# SCH_updated.net
KiCad netlist of a schematic drawn in EasyEDA
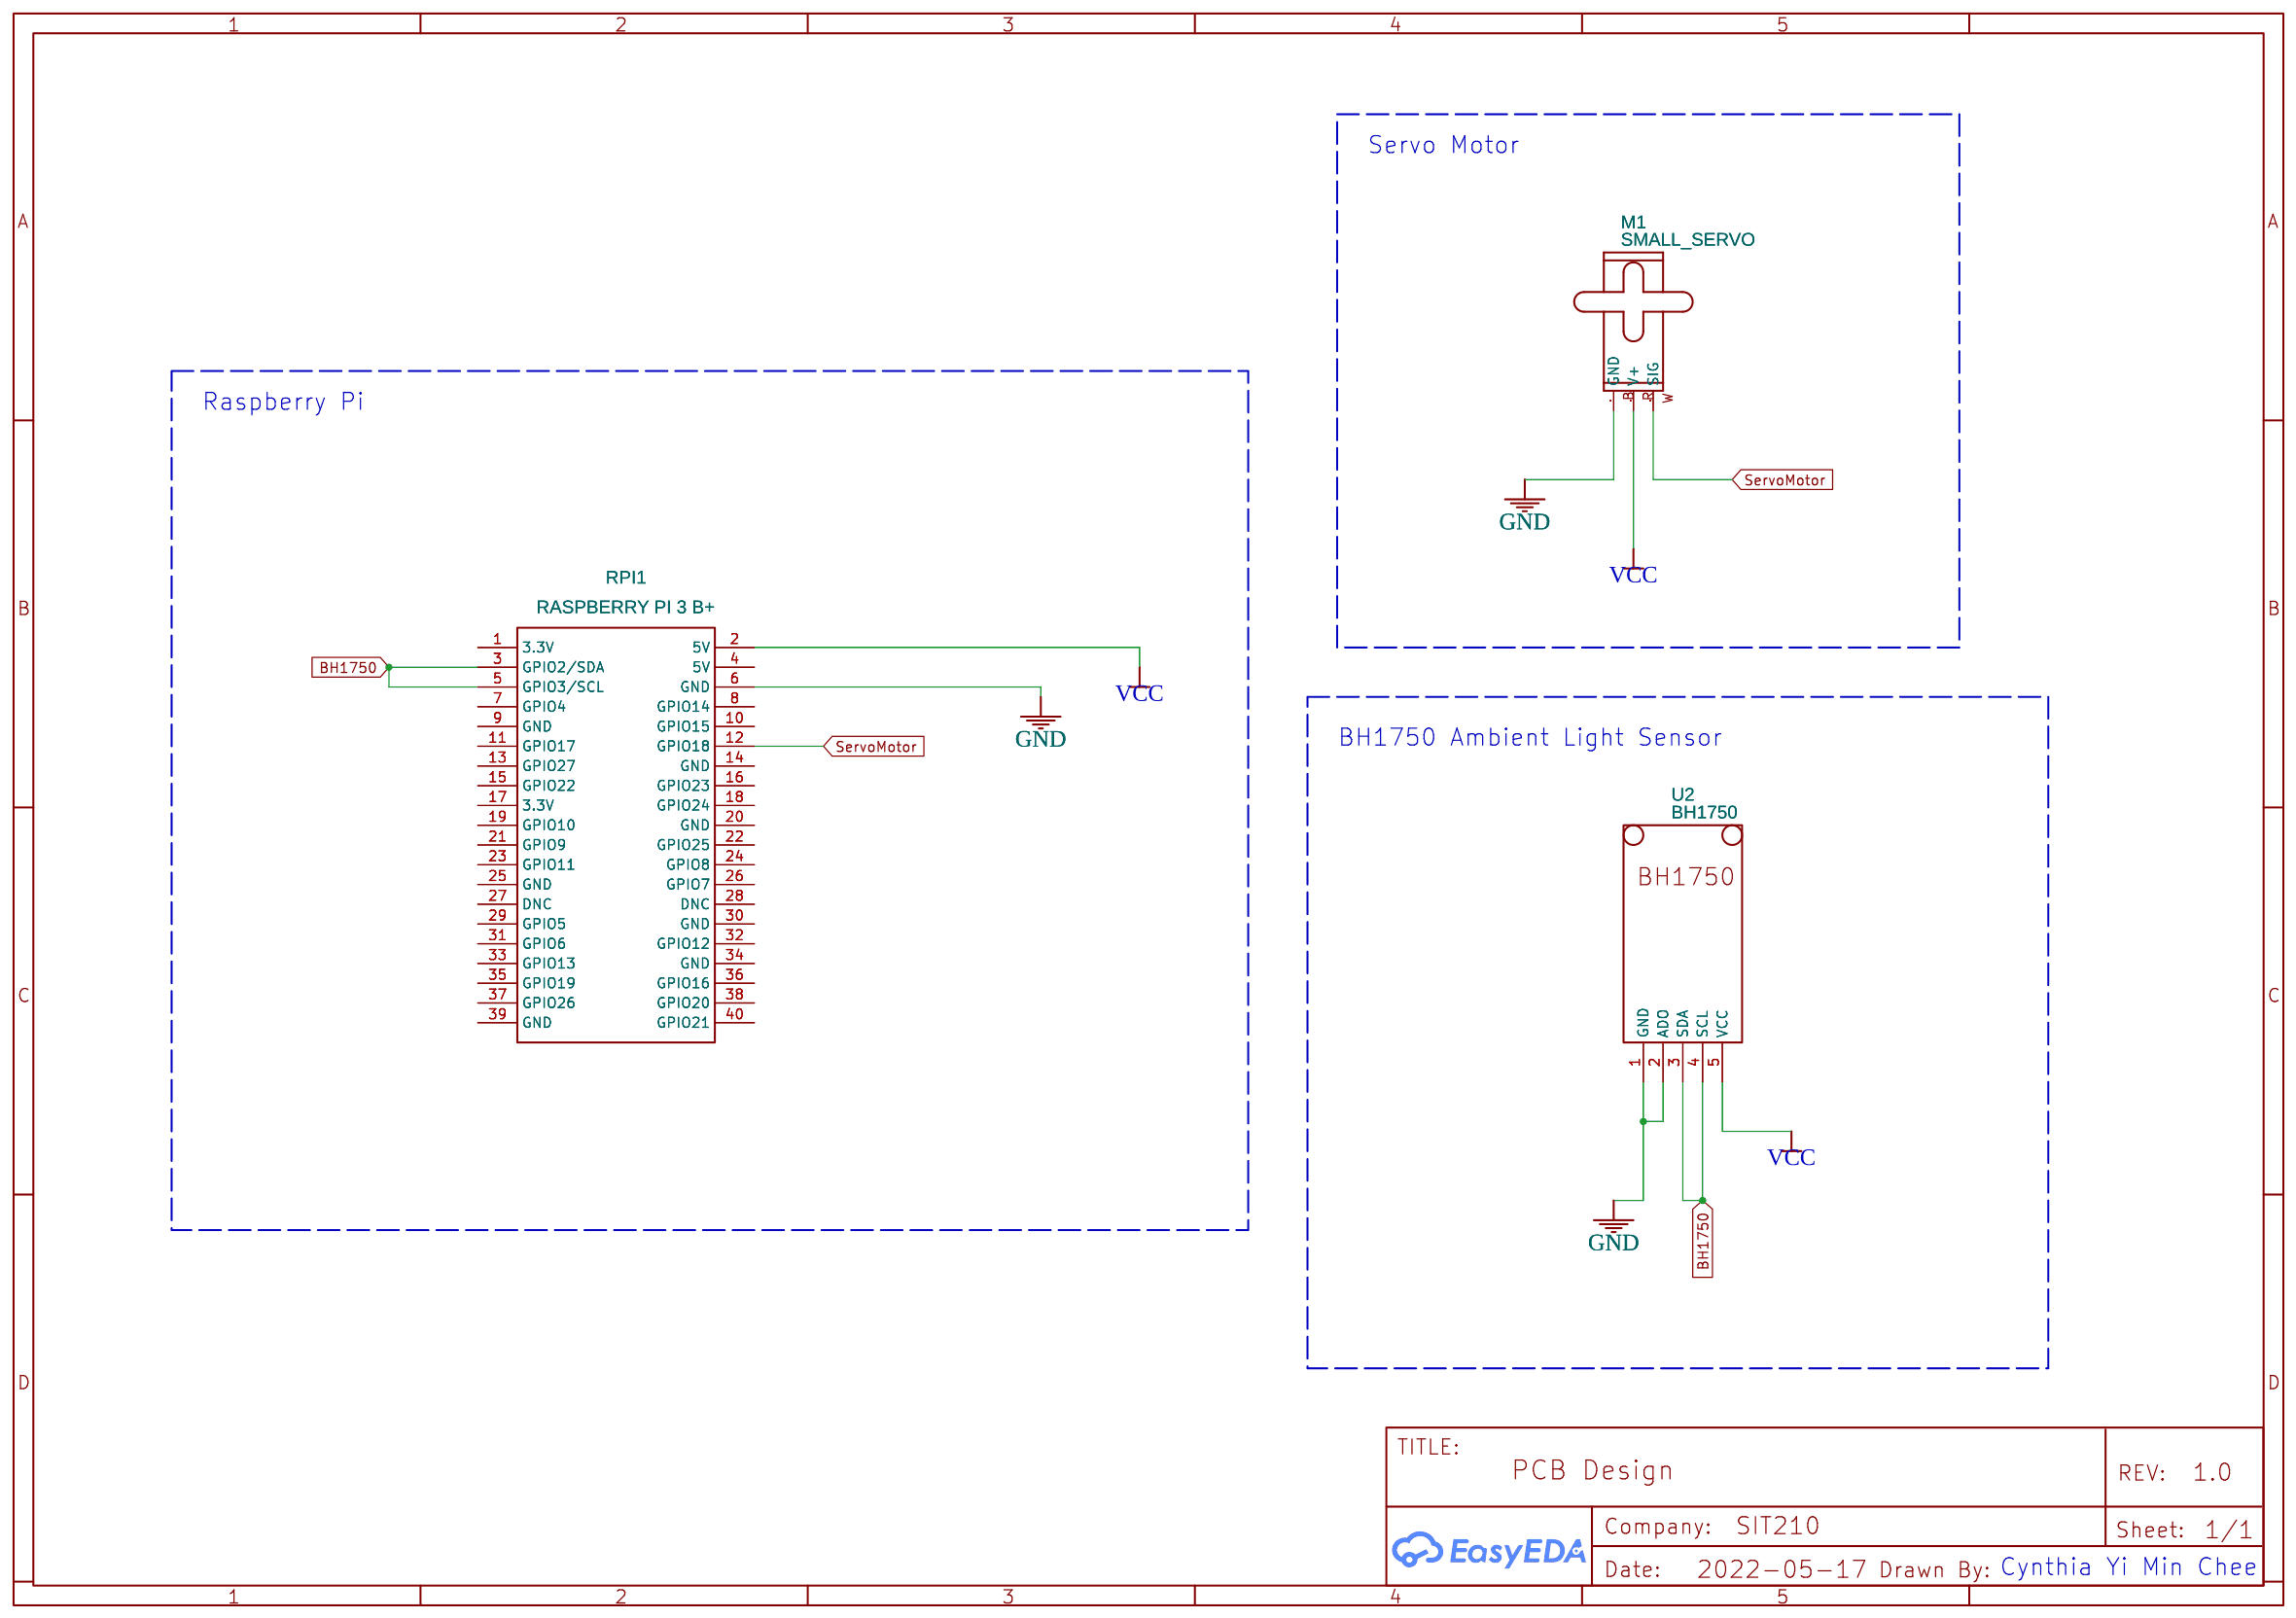
[diagram p0: Sheet_1]
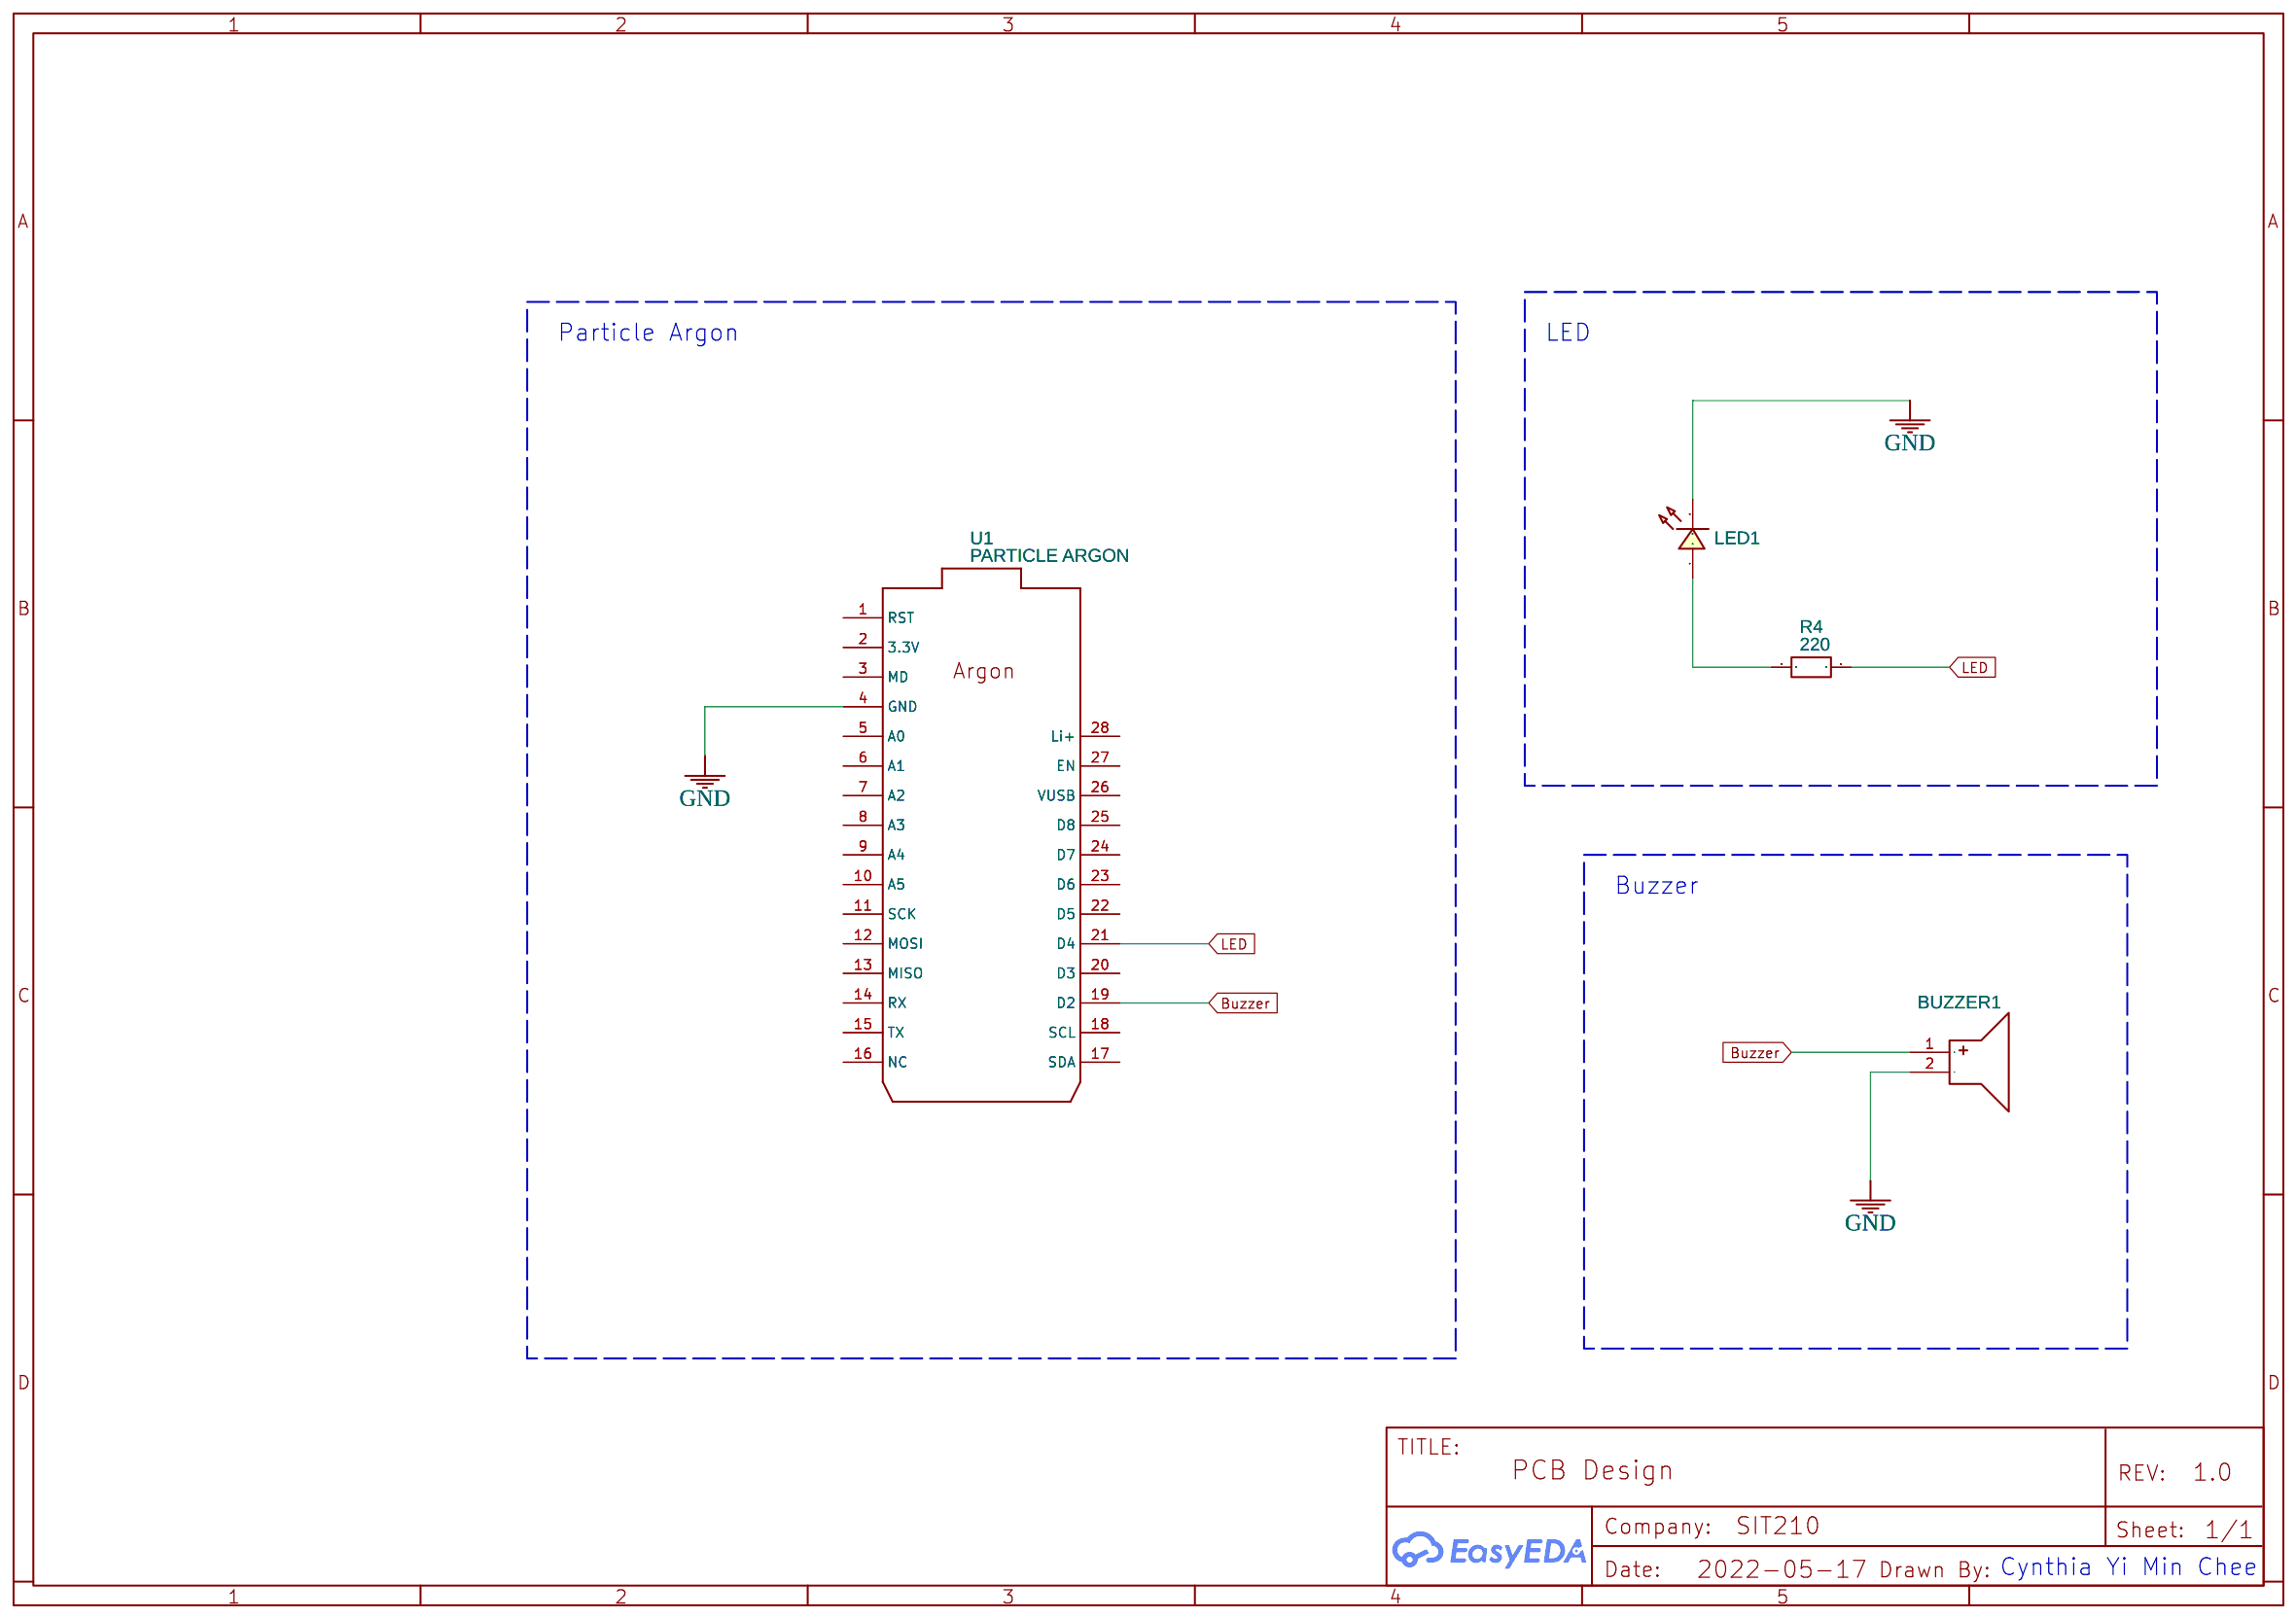
[diagram p1: Sheet_2]

(export (version "E")
  (design (tool "Eeschema 10.0.6"))
  (components
    (comp (ref "M1") (value "SMALL_SERVO") (libsource (lib "") (part "SMALL_SERVO")))
    (comp (ref "RPI1")
      (value "RASPBERRY PI 3 B+")
      (fields
        (field (name "Manufacturer") "Raspberry Pi")
        (field (name "BOM_Manufacturer Part") "Raspberry Pi 3 - Model B+ - 1.4GHz Cortex-A53 with 1GB RAM")
        (field (name "BOM_Supplier Part") "3775")
      )
      (libsource (lib "") (part "RASPBERRY PI 3 B+"))
    )
    (comp (ref "U2") (value "BH1750") (libsource (lib "") (part "BH1750")))
    (comp (ref "BUZZER1")
      (value "BUZZER.9032")
      (fields (field (name "BOM_Supplier Part") "C9900002564"))
      (libsource (lib "") (part "BUZZER.9032"))
    )
    (comp (ref "LED1")
      (value "LED-0603_R")
      (fields
        (field (name "BOM_Manufacturer Part") "19-217/R6C-AL1M2VY/3T")
        (field (name "BOM_Supplier Part") "C72044")
      )
      (libsource (lib "") (part "LED-0603_R"))
    )
    (comp (ref "R4") (value "220") (libsource (lib "") (part "R_0603_EU")))
    (comp (ref "U1")
      (value "PARTICLE ARGON")
      (fields (field (name "BOM_Manufacturer Part") "Particle Argon"))
      (libsource (lib "") (part "PARTICLE ARGON"))
    )
  )
  (nets
    (net (code "1") (name "BH1750") (class "Default")
      (node (ref "RPI1") (pin "3") (pinfunction "GPIO2/SDA_3") (pintype "bidirectional"))
      (node (ref "RPI1") (pin "5") (pinfunction "GPIO3/SCL_5") (pintype "bidirectional"))
      (node (ref "U2") (pin "3") (pinfunction "SDA_3") (pintype "unspecified"))
      (node (ref "U2") (pin "4") (pinfunction "SCL_4") (pintype "unspecified"))
    )
    (net (code "2") (name "Buzzer") (class "Default")
      (node (ref "BUZZER1") (pin "1") (pinfunction "+_1") (pintype "unspecified"))
      (node (ref "U1") (pin "19") (pinfunction "D2_19") (pintype "unspecified"))
    )
    (net (code "3") (name "GND") (class "Default")
      (node (ref "BUZZER1") (pin "2") (pinfunction "-_2") (pintype "unspecified"))
      (node (ref "LED1") (pin "2") (pinfunction "2_2") (pintype "unspecified"))
      (node (ref "M1") (pin "3") (pinfunction "GND_3") (pintype "unspecified"))
      (node (ref "RPI1") (pin "6") (pinfunction "GND_6") (pintype "unspecified"))
      (node (ref "U1") (pin "4") (pinfunction "GND_4") (pintype "unspecified"))
      (node (ref "U2") (pin "1") (pinfunction "GND_1") (pintype "unspecified"))
      (node (ref "U2") (pin "2") (pinfunction "ADO_2") (pintype "unspecified"))
    )
    (net (code "4") (name "LED") (class "Default")
      (node (ref "R4") (pin "1") (pinfunction "1_1") (pintype "unspecified"))
      (node (ref "U1") (pin "21") (pinfunction "D4_21") (pintype "unspecified"))
    )
    (net (code "5") (name "Net-(LED1-Pad1)") (class "Default")
      (node (ref "LED1") (pin "1") (pinfunction "1_1") (pintype "unspecified"))
      (node (ref "R4") (pin "2") (pinfunction "2_2") (pintype "unspecified"))
    )
    (net (code "6") (name "ServoMotor") (class "Default")
      (node (ref "M1") (pin "1") (pinfunction "SIG_1") (pintype "unspecified"))
      (node (ref "RPI1") (pin "12") (pinfunction "GPIO18_12") (pintype "bidirectional"))
    )
    (net (code "7") (name "VCC") (class "Default")
      (node (ref "M1") (pin "2") (pinfunction "V+_2") (pintype "unspecified"))
      (node (ref "RPI1") (pin "2") (pinfunction "5V_2") (pintype "passive"))
      (node (ref "U2") (pin "5") (pinfunction "VCC_5") (pintype "unspecified"))
    )
    (net (code "8") (name "unconnected-(RPI1-3.3V-Pad1)") (class "Default")
      (node (ref "RPI1") (pin "1") (pinfunction "3.3V_1") (pintype "passive"))
    )
    (net (code "9") (name "unconnected-(RPI1-3.3V-Pad17)") (class "Default")
      (node (ref "RPI1") (pin "17") (pinfunction "3.3V_17") (pintype "passive"))
    )
    (net (code "10") (name "unconnected-(RPI1-5V-Pad4)") (class "Default")
      (node (ref "RPI1") (pin "4") (pinfunction "5V_4") (pintype "passive"))
    )
    (net (code "11") (name "unconnected-(RPI1-DNC-Pad27)") (class "Default")
      (node (ref "RPI1") (pin "27") (pinfunction "DNC_27") (pintype "unspecified"))
    )
    (net (code "12") (name "unconnected-(RPI1-DNC-Pad28)") (class "Default")
      (node (ref "RPI1") (pin "28") (pinfunction "DNC_28") (pintype "unspecified"))
    )
    (net (code "13") (name "unconnected-(RPI1-GND-Pad9)") (class "Default")
      (node (ref "RPI1") (pin "9") (pinfunction "GND_9") (pintype "unspecified"))
    )
    (net (code "14") (name "unconnected-(RPI1-GND-Pad14)") (class "Default")
      (node (ref "RPI1") (pin "14") (pinfunction "GND_14") (pintype "unspecified"))
    )
    (net (code "15") (name "unconnected-(RPI1-GND-Pad20)") (class "Default")
      (node (ref "RPI1") (pin "20") (pinfunction "GND_20") (pintype "unspecified"))
    )
    (net (code "16") (name "unconnected-(RPI1-GND-Pad25)") (class "Default")
      (node (ref "RPI1") (pin "25") (pinfunction "GND_25") (pintype "unspecified"))
    )
    (net (code "17") (name "unconnected-(RPI1-GND-Pad30)") (class "Default")
      (node (ref "RPI1") (pin "30") (pinfunction "GND_30") (pintype "unspecified"))
    )
    (net (code "18") (name "unconnected-(RPI1-GND-Pad34)") (class "Default")
      (node (ref "RPI1") (pin "34") (pinfunction "GND_34") (pintype "unspecified"))
    )
    (net (code "19") (name "unconnected-(RPI1-GND-Pad39)") (class "Default")
      (node (ref "RPI1") (pin "39") (pinfunction "GND_39") (pintype "unspecified"))
    )
    (net (code "20") (name "unconnected-(RPI1-GPIO4-Pad7)") (class "Default")
      (node (ref "RPI1") (pin "7") (pinfunction "GPIO4_7") (pintype "bidirectional"))
    )
    (net (code "21") (name "unconnected-(RPI1-GPIO5-Pad29)") (class "Default")
      (node (ref "RPI1") (pin "29") (pinfunction "GPIO5_29") (pintype "bidirectional"))
    )
    (net (code "22") (name "unconnected-(RPI1-GPIO6-Pad31)") (class "Default")
      (node (ref "RPI1") (pin "31") (pinfunction "GPIO6_31") (pintype "bidirectional"))
    )
    (net (code "23") (name "unconnected-(RPI1-GPIO7-Pad26)") (class "Default")
      (node (ref "RPI1") (pin "26") (pinfunction "GPIO7_26") (pintype "bidirectional"))
    )
    (net (code "24") (name "unconnected-(RPI1-GPIO8-Pad24)") (class "Default")
      (node (ref "RPI1") (pin "24") (pinfunction "GPIO8_24") (pintype "bidirectional"))
    )
    (net (code "25") (name "unconnected-(RPI1-GPIO9-Pad21)") (class "Default")
      (node (ref "RPI1") (pin "21") (pinfunction "GPIO9_21") (pintype "bidirectional"))
    )
    (net (code "26") (name "unconnected-(RPI1-GPIO10-Pad19)") (class "Default")
      (node (ref "RPI1") (pin "19") (pinfunction "GPIO10_19") (pintype "bidirectional"))
    )
    (net (code "27") (name "unconnected-(RPI1-GPIO11-Pad23)") (class "Default")
      (node (ref "RPI1") (pin "23") (pinfunction "GPIO11_23") (pintype "bidirectional"))
    )
    (net (code "28") (name "unconnected-(RPI1-GPIO12-Pad32)") (class "Default")
      (node (ref "RPI1") (pin "32") (pinfunction "GPIO12_32") (pintype "bidirectional"))
    )
    (net (code "29") (name "unconnected-(RPI1-GPIO13-Pad33)") (class "Default")
      (node (ref "RPI1") (pin "33") (pinfunction "GPIO13_33") (pintype "bidirectional"))
    )
    (net (code "30") (name "unconnected-(RPI1-GPIO14-Pad8)") (class "Default")
      (node (ref "RPI1") (pin "8") (pinfunction "GPIO14_8") (pintype "bidirectional"))
    )
    (net (code "31") (name "unconnected-(RPI1-GPIO15-Pad10)") (class "Default")
      (node (ref "RPI1") (pin "10") (pinfunction "GPIO15_10") (pintype "bidirectional"))
    )
    (net (code "32") (name "unconnected-(RPI1-GPIO16-Pad36)") (class "Default")
      (node (ref "RPI1") (pin "36") (pinfunction "GPIO16_36") (pintype "bidirectional"))
    )
    (net (code "33") (name "unconnected-(RPI1-GPIO17-Pad11)") (class "Default")
      (node (ref "RPI1") (pin "11") (pinfunction "GPIO17_11") (pintype "bidirectional"))
    )
    (net (code "34") (name "unconnected-(RPI1-GPIO19-Pad35)") (class "Default")
      (node (ref "RPI1") (pin "35") (pinfunction "GPIO19_35") (pintype "bidirectional"))
    )
    (net (code "35") (name "unconnected-(RPI1-GPIO20-Pad38)") (class "Default")
      (node (ref "RPI1") (pin "38") (pinfunction "GPIO20_38") (pintype "bidirectional"))
    )
    (net (code "36") (name "unconnected-(RPI1-GPIO21-Pad40)") (class "Default")
      (node (ref "RPI1") (pin "40") (pinfunction "GPIO21_40") (pintype "bidirectional"))
    )
    (net (code "37") (name "unconnected-(RPI1-GPIO22-Pad15)") (class "Default")
      (node (ref "RPI1") (pin "15") (pinfunction "GPIO22_15") (pintype "bidirectional"))
    )
    (net (code "38") (name "unconnected-(RPI1-GPIO23-Pad16)") (class "Default")
      (node (ref "RPI1") (pin "16") (pinfunction "GPIO23_16") (pintype "bidirectional"))
    )
    (net (code "39") (name "unconnected-(RPI1-GPIO24-Pad18)") (class "Default")
      (node (ref "RPI1") (pin "18") (pinfunction "GPIO24_18") (pintype "bidirectional"))
    )
    (net (code "40") (name "unconnected-(RPI1-GPIO25-Pad22)") (class "Default")
      (node (ref "RPI1") (pin "22") (pinfunction "GPIO25_22") (pintype "bidirectional"))
    )
    (net (code "41") (name "unconnected-(RPI1-GPIO26-Pad37)") (class "Default")
      (node (ref "RPI1") (pin "37") (pinfunction "GPIO26_37") (pintype "bidirectional"))
    )
    (net (code "42") (name "unconnected-(RPI1-GPIO27-Pad13)") (class "Default")
      (node (ref "RPI1") (pin "13") (pinfunction "GPIO27_13") (pintype "bidirectional"))
    )
    (net (code "43") (name "unconnected-(U1-3.3V-Pad2)") (class "Default")
      (node (ref "U1") (pin "2") (pinfunction "3.3V_2") (pintype "unspecified"))
    )
    (net (code "44") (name "unconnected-(U1-A0-Pad5)") (class "Default")
      (node (ref "U1") (pin "5") (pinfunction "A0_5") (pintype "unspecified"))
    )
    (net (code "45") (name "unconnected-(U1-A1-Pad6)") (class "Default")
      (node (ref "U1") (pin "6") (pinfunction "A1_6") (pintype "unspecified"))
    )
    (net (code "46") (name "unconnected-(U1-A2-Pad7)") (class "Default")
      (node (ref "U1") (pin "7") (pinfunction "A2_7") (pintype "unspecified"))
    )
    (net (code "47") (name "unconnected-(U1-A3-Pad8)") (class "Default")
      (node (ref "U1") (pin "8") (pinfunction "A3_8") (pintype "unspecified"))
    )
    (net (code "48") (name "unconnected-(U1-A4-Pad9)") (class "Default")
      (node (ref "U1") (pin "9") (pinfunction "A4_9") (pintype "unspecified"))
    )
    (net (code "49") (name "unconnected-(U1-A5-Pad10)") (class "Default")
      (node (ref "U1") (pin "10") (pinfunction "A5_10") (pintype "unspecified"))
    )
    (net (code "50") (name "unconnected-(U1-D3-Pad20)") (class "Default")
      (node (ref "U1") (pin "20") (pinfunction "D3_20") (pintype "unspecified"))
    )
    (net (code "51") (name "unconnected-(U1-D5-Pad22)") (class "Default")
      (node (ref "U1") (pin "22") (pinfunction "D5_22") (pintype "unspecified"))
    )
    (net (code "52") (name "unconnected-(U1-D6-Pad23)") (class "Default")
      (node (ref "U1") (pin "23") (pinfunction "D6_23") (pintype "unspecified"))
    )
    (net (code "53") (name "unconnected-(U1-D7-Pad24)") (class "Default")
      (node (ref "U1") (pin "24") (pinfunction "D7_24") (pintype "unspecified"))
    )
    (net (code "54") (name "unconnected-(U1-D8-Pad25)") (class "Default")
      (node (ref "U1") (pin "25") (pinfunction "D8_25") (pintype "unspecified"))
    )
    (net (code "55") (name "unconnected-(U1-EN-Pad27)") (class "Default")
      (node (ref "U1") (pin "27") (pinfunction "EN_27") (pintype "unspecified"))
    )
    (net (code "56") (name "unconnected-(U1-Li+-Pad28)") (class "Default")
      (node (ref "U1") (pin "28") (pinfunction "Li+_28") (pintype "unspecified"))
    )
    (net (code "57") (name "unconnected-(U1-MD-Pad3)") (class "Default")
      (node (ref "U1") (pin "3") (pinfunction "MD_3") (pintype "unspecified"))
    )
    (net (code "58") (name "unconnected-(U1-MISO-Pad13)") (class "Default")
      (node (ref "U1") (pin "13") (pinfunction "MISO_13") (pintype "unspecified"))
    )
    (net (code "59") (name "unconnected-(U1-MOSI-Pad12)") (class "Default")
      (node (ref "U1") (pin "12") (pinfunction "MOSI_12") (pintype "unspecified"))
    )
    (net (code "60") (name "unconnected-(U1-NC-Pad16)") (class "Default")
      (node (ref "U1") (pin "16") (pinfunction "NC_16") (pintype "unspecified"))
    )
    (net (code "61") (name "unconnected-(U1-RST-Pad1)") (class "Default")
      (node (ref "U1") (pin "1") (pinfunction "RST_1") (pintype "unspecified"))
    )
    (net (code "62") (name "unconnected-(U1-RX-Pad14)") (class "Default")
      (node (ref "U1") (pin "14") (pinfunction "RX_14") (pintype "unspecified"))
    )
    (net (code "63") (name "unconnected-(U1-SCK-Pad11)") (class "Default")
      (node (ref "U1") (pin "11") (pinfunction "SCK_11") (pintype "unspecified"))
    )
    (net (code "64") (name "unconnected-(U1-SCL-Pad18)") (class "Default")
      (node (ref "U1") (pin "18") (pinfunction "SCL_18") (pintype "unspecified"))
    )
    (net (code "65") (name "unconnected-(U1-SDA-Pad17)") (class "Default")
      (node (ref "U1") (pin "17") (pinfunction "SDA_17") (pintype "unspecified"))
    )
    (net (code "66") (name "unconnected-(U1-TX-Pad15)") (class "Default")
      (node (ref "U1") (pin "15") (pinfunction "TX_15") (pintype "unspecified"))
    )
    (net (code "67") (name "unconnected-(U1-VUSB-Pad26)") (class "Default")
      (node (ref "U1") (pin "26") (pinfunction "VUSB_26") (pintype "unspecified"))
    )
  )
)
